# Sheet1.net
KiCad netlist of a schematic drawn in Altium Designer
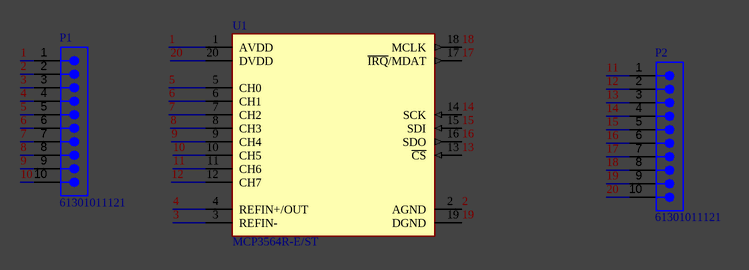
[diagram p0: Sheet1.SchDoc]

(export (version "E")
  (design (tool "Eeschema 10.0.6"))
  (components
    (comp (ref "P1")
      (value "61301011121")
      (footprint "61301011121")
      (libsource (lib "Altium Content Vault") (part "Header_Male_1R_10P"))
    )
    (comp (ref "P2")
      (value "61301011121")
      (footprint "61301011121")
      (libsource (lib "Altium Content Vault") (part "Header_Male_1R_10P"))
    )
    (comp (ref "U1")
      (value "MCP3564R-E/ST")
      (footprint "FP-C04-088-MFG")
      (description "MCP3564R-E/ST 8-Channel Single ADC Delta-Sigma 153.6ksps 24-bit Serial 20-Pin TSSOP Tube")
      (libsource (lib "Altium Content Vault") (part "0ac5b573d1d2d90c3815fbc455c1358"))
    )
  )
  (nets
    (net (code "1") (name "/1") (class "Default")
      (node (ref "P1") (pin "1") (pinfunction "1_1") (pintype "passive"))
      (node (ref "U1") (pin "1") (pinfunction "AVDD_1") (pintype "power_in"))
    )
    (net (code "2") (name "/2") (class "Default")
      (node (ref "P1") (pin "2") (pinfunction "2_2") (pintype "passive"))
      (node (ref "U1") (pin "2") (pinfunction "AGND_2") (pintype "power_in"))
    )
    (net (code "3") (name "/3") (class "Default")
      (node (ref "P1") (pin "3") (pinfunction "3_3") (pintype "passive"))
      (node (ref "U1") (pin "3") (pinfunction "REFIN-_3") (pintype "passive"))
    )
    (net (code "4") (name "/4") (class "Default")
      (node (ref "P1") (pin "4") (pinfunction "4_4") (pintype "passive"))
      (node (ref "U1") (pin "4") (pinfunction "REFIN+/OUT_4") (pintype "passive"))
    )
    (net (code "5") (name "/5") (class "Default")
      (node (ref "P1") (pin "5") (pinfunction "5_5") (pintype "passive"))
      (node (ref "U1") (pin "5") (pinfunction "CH0_5") (pintype "passive"))
    )
    (net (code "6") (name "/6") (class "Default")
      (node (ref "P1") (pin "6") (pinfunction "6_6") (pintype "passive"))
      (node (ref "U1") (pin "6") (pinfunction "CH1_6") (pintype "passive"))
    )
    (net (code "7") (name "/7") (class "Default")
      (node (ref "P1") (pin "7") (pinfunction "7_7") (pintype "passive"))
      (node (ref "U1") (pin "7") (pinfunction "CH2_7") (pintype "passive"))
    )
    (net (code "8") (name "/8") (class "Default")
      (node (ref "P1") (pin "8") (pinfunction "8_8") (pintype "passive"))
      (node (ref "U1") (pin "8") (pinfunction "CH3_8") (pintype "passive"))
    )
    (net (code "9") (name "/9") (class "Default")
      (node (ref "P1") (pin "9") (pinfunction "9_9") (pintype "passive"))
      (node (ref "U1") (pin "9") (pinfunction "CH4_9") (pintype "passive"))
    )
    (net (code "10") (name "/10") (class "Default")
      (node (ref "P1") (pin "10") (pinfunction "10_10") (pintype "passive"))
      (node (ref "U1") (pin "10") (pinfunction "CH5_10") (pintype "passive"))
    )
    (net (code "11") (name "/11") (class "Default")
      (node (ref "P2") (pin "1") (pinfunction "1_1") (pintype "passive"))
      (node (ref "U1") (pin "11") (pinfunction "CH6_11") (pintype "passive"))
    )
    (net (code "12") (name "/12") (class "Default")
      (node (ref "P2") (pin "2") (pinfunction "2_2") (pintype "passive"))
      (node (ref "U1") (pin "12") (pinfunction "CH7_12") (pintype "passive"))
    )
    (net (code "13") (name "/13") (class "Default")
      (node (ref "P2") (pin "3") (pinfunction "3_3") (pintype "passive"))
      (node (ref "U1") (pin "13") (pinfunction "~{CS}_13") (pintype "input"))
    )
    (net (code "14") (name "/14") (class "Default")
      (node (ref "P2") (pin "4") (pinfunction "4_4") (pintype "passive"))
      (node (ref "U1") (pin "14") (pinfunction "SCK_14") (pintype "input"))
    )
    (net (code "15") (name "/15") (class "Default")
      (node (ref "P2") (pin "5") (pinfunction "5_5") (pintype "passive"))
      (node (ref "U1") (pin "15") (pinfunction "SDI_15") (pintype "input"))
    )
    (net (code "16") (name "/16") (class "Default")
      (node (ref "P2") (pin "6") (pinfunction "6_6") (pintype "passive"))
      (node (ref "U1") (pin "16") (pinfunction "SDO_16") (pintype "output"))
    )
    (net (code "17") (name "/17") (class "Default")
      (node (ref "P2") (pin "7") (pinfunction "7_7") (pintype "passive"))
      (node (ref "U1") (pin "17") (pinfunction "~{IRQ}/MDAT_17") (pintype "output"))
    )
    (net (code "18") (name "/18") (class "Default")
      (node (ref "P2") (pin "8") (pinfunction "8_8") (pintype "passive"))
      (node (ref "U1") (pin "18") (pinfunction "MCLK_18") (pintype "output"))
    )
    (net (code "19") (name "/19") (class "Default")
      (node (ref "P2") (pin "9") (pinfunction "9_9") (pintype "passive"))
      (node (ref "U1") (pin "19") (pinfunction "DGND_19") (pintype "power_in"))
    )
    (net (code "20") (name "/20") (class "Default")
      (node (ref "P2") (pin "10") (pinfunction "10_10") (pintype "passive"))
      (node (ref "U1") (pin "20") (pinfunction "DVDD_20") (pintype "power_in"))
    )
  )
)
